# TC1014.net
KiCad netlist of a schematic drawn in EAGLE
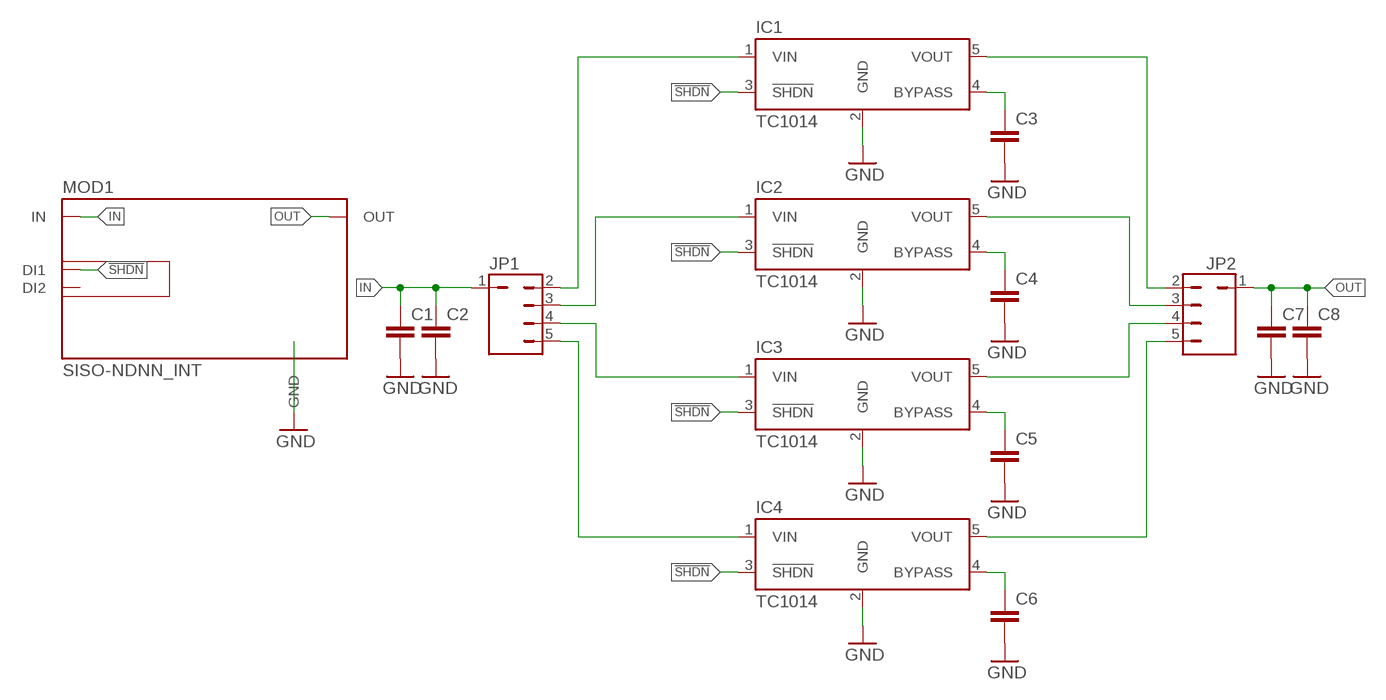
[diagram p0: schematic, sheet 1]

(export (version "E")
  (design (tool "Eeschema 10.0.6"))
  (components
    (comp (ref "C1")
      (value "C-EUC0805")
      (footprint "eagle-import:C0805")
      (libsource (lib "eagle-import") (part "C-EUC0805"))
    )
    (comp (ref "C2")
      (value "C-EUC0805")
      (footprint "eagle-import:C0805")
      (libsource (lib "eagle-import") (part "C-EUC0805"))
    )
    (comp (ref "C3")
      (value "C-EUC0805")
      (footprint "eagle-import:C0805")
      (libsource (lib "eagle-import") (part "C-EUC0805"))
    )
    (comp (ref "C4")
      (value "C-EUC0805")
      (footprint "eagle-import:C0805")
      (libsource (lib "eagle-import") (part "C-EUC0805"))
    )
    (comp (ref "C5")
      (value "C-EUC0805")
      (footprint "eagle-import:C0805")
      (libsource (lib "eagle-import") (part "C-EUC0805"))
    )
    (comp (ref "C6")
      (value "C-EUC0805")
      (footprint "eagle-import:C0805")
      (libsource (lib "eagle-import") (part "C-EUC0805"))
    )
    (comp (ref "C7")
      (value "C-EUC0805")
      (footprint "eagle-import:C0805")
      (libsource (lib "eagle-import") (part "C-EUC0805"))
    )
    (comp (ref "C8")
      (value "C-EUC0805")
      (footprint "eagle-import:C0805")
      (libsource (lib "eagle-import") (part "C-EUC0805"))
    )
    (comp (ref "IC1")
      (value "TC1014")
      (footprint "eagle-import:SOT23-5")
      (libsource (lib "eagle-import") (part "TC1014"))
    )
    (comp (ref "IC2")
      (value "TC1014")
      (footprint "eagle-import:SOT23-5")
      (libsource (lib "eagle-import") (part "TC1014"))
    )
    (comp (ref "IC3")
      (value "TC1014")
      (footprint "eagle-import:SOT23-5")
      (libsource (lib "eagle-import") (part "TC1014"))
    )
    (comp (ref "IC4")
      (value "TC1014")
      (footprint "eagle-import:SOT23-5")
      (libsource (lib "eagle-import") (part "TC1014"))
    )
    (comp (ref "JP1")
      (value "JP4Q")
      (footprint "eagle-import:JP1-4")
      (libsource (lib "eagle-import") (part "JP4Q"))
    )
    (comp (ref "JP2")
      (value "JP4Q")
      (footprint "eagle-import:JP1-4")
      (libsource (lib "eagle-import") (part "JP4Q"))
    )
    (comp (ref "MOD1")
      (value "SISO-NDNN_INT")
      (footprint "eagle-import:SISO-NDNN")
      (libsource (lib "eagle-import") (part "SISO-NDNN_INT"))
    )
  )
  (nets
    (net (code "1") (name "/~{SHDN}") (class "Default")
      (node (ref "IC1") (pin "3") (pinfunction "~{SHDN}_3") (pintype "input"))
      (node (ref "IC2") (pin "3") (pinfunction "~{SHDN}_3") (pintype "input"))
      (node (ref "IC3") (pin "3") (pinfunction "~{SHDN}_3") (pintype "input"))
      (node (ref "IC4") (pin "3") (pinfunction "~{SHDN}_3") (pintype "input"))
      (node (ref "MOD1") (pin "DI1") (pinfunction "DI1_DI1") (pintype "output"))
    )
    (net (code "2") (name "GND") (class "Default")
      (node (ref "C1") (pin "2") (pinfunction "2_2") (pintype "passive"))
      (node (ref "C2") (pin "2") (pinfunction "2_2") (pintype "passive"))
      (node (ref "C3") (pin "2") (pinfunction "2_2") (pintype "passive"))
      (node (ref "C4") (pin "2") (pinfunction "2_2") (pintype "passive"))
      (node (ref "C5") (pin "2") (pinfunction "2_2") (pintype "passive"))
      (node (ref "C6") (pin "2") (pinfunction "2_2") (pintype "passive"))
      (node (ref "C7") (pin "2") (pinfunction "2_2") (pintype "passive"))
      (node (ref "C8") (pin "2") (pinfunction "2_2") (pintype "passive"))
      (node (ref "IC1") (pin "2") (pinfunction "GND_2") (pintype "power_in"))
      (node (ref "IC2") (pin "2") (pinfunction "GND_2") (pintype "power_in"))
      (node (ref "IC3") (pin "2") (pinfunction "GND_2") (pintype "power_in"))
      (node (ref "IC4") (pin "2") (pinfunction "GND_2") (pintype "power_in"))
      (node (ref "MOD1") (pin "GND1") (pinfunction "GND_GND1") (pintype "power_in"))
      (node (ref "MOD1") (pin "GND2") (pinfunction "GND_GND2") (pintype "power_in"))
      (node (ref "MOD1") (pin "GND3") (pinfunction "GND_GND3") (pintype "power_in"))
      (node (ref "MOD1") (pin "GND4") (pinfunction "GND_GND4") (pintype "power_in"))
    )
    (net (code "3") (name "IN") (class "Default")
      (node (ref "C1") (pin "1") (pinfunction "1_1") (pintype "passive"))
      (node (ref "C2") (pin "1") (pinfunction "1_1") (pintype "passive"))
      (node (ref "JP1") (pin "1") (pinfunction "1_1") (pintype "passive"))
      (node (ref "MOD1") (pin "IN1") (pinfunction "IN_IN1") (pintype "output"))
      (node (ref "MOD1") (pin "IN2") (pinfunction "IN_IN2") (pintype "output"))
      (node (ref "MOD1") (pin "IN3") (pinfunction "IN_IN3") (pintype "output"))
      (node (ref "MOD1") (pin "IN4") (pinfunction "IN_IN4") (pintype "output"))
    )
    (net (code "4") (name "Net-(IC1-BYPASS)") (class "Default")
      (node (ref "C3") (pin "1") (pinfunction "1_1") (pintype "passive"))
      (node (ref "IC1") (pin "4") (pinfunction "BYPASS_4") (pintype "bidirectional"))
    )
    (net (code "5") (name "Net-(IC1-VIN)") (class "Default")
      (node (ref "IC1") (pin "1") (pinfunction "VIN_1") (pintype "power_in"))
      (node (ref "JP1") (pin "2") (pinfunction "2_2") (pintype "passive"))
    )
    (net (code "6") (name "Net-(IC1-VOUT)") (class "Default")
      (node (ref "IC1") (pin "5") (pinfunction "VOUT_5") (pintype "power_in"))
      (node (ref "JP2") (pin "2") (pinfunction "2_2") (pintype "passive"))
    )
    (net (code "7") (name "Net-(IC2-BYPASS)") (class "Default")
      (node (ref "C4") (pin "1") (pinfunction "1_1") (pintype "passive"))
      (node (ref "IC2") (pin "4") (pinfunction "BYPASS_4") (pintype "bidirectional"))
    )
    (net (code "8") (name "Net-(IC2-VIN)") (class "Default")
      (node (ref "IC2") (pin "1") (pinfunction "VIN_1") (pintype "power_in"))
      (node (ref "JP1") (pin "3") (pinfunction "3_3") (pintype "passive"))
    )
    (net (code "9") (name "Net-(IC2-VOUT)") (class "Default")
      (node (ref "IC2") (pin "5") (pinfunction "VOUT_5") (pintype "power_in"))
      (node (ref "JP2") (pin "3") (pinfunction "3_3") (pintype "passive"))
    )
    (net (code "10") (name "Net-(IC3-BYPASS)") (class "Default")
      (node (ref "C5") (pin "1") (pinfunction "1_1") (pintype "passive"))
      (node (ref "IC3") (pin "4") (pinfunction "BYPASS_4") (pintype "bidirectional"))
    )
    (net (code "11") (name "Net-(IC3-VIN)") (class "Default")
      (node (ref "IC3") (pin "1") (pinfunction "VIN_1") (pintype "power_in"))
      (node (ref "JP1") (pin "4") (pinfunction "4_4") (pintype "passive"))
    )
    (net (code "12") (name "Net-(IC3-VOUT)") (class "Default")
      (node (ref "IC3") (pin "5") (pinfunction "VOUT_5") (pintype "power_in"))
      (node (ref "JP2") (pin "4") (pinfunction "4_4") (pintype "passive"))
    )
    (net (code "13") (name "Net-(IC4-BYPASS)") (class "Default")
      (node (ref "C6") (pin "1") (pinfunction "1_1") (pintype "passive"))
      (node (ref "IC4") (pin "4") (pinfunction "BYPASS_4") (pintype "bidirectional"))
    )
    (net (code "14") (name "Net-(IC4-VIN)") (class "Default")
      (node (ref "IC4") (pin "1") (pinfunction "VIN_1") (pintype "power_in"))
      (node (ref "JP1") (pin "5") (pinfunction "5_5") (pintype "passive"))
    )
    (net (code "15") (name "Net-(IC4-VOUT)") (class "Default")
      (node (ref "IC4") (pin "5") (pinfunction "VOUT_5") (pintype "power_in"))
      (node (ref "JP2") (pin "5") (pinfunction "5_5") (pintype "passive"))
    )
    (net (code "16") (name "OUT") (class "Default")
      (node (ref "C7") (pin "1") (pinfunction "1_1") (pintype "passive"))
      (node (ref "C8") (pin "1") (pinfunction "1_1") (pintype "passive"))
      (node (ref "JP2") (pin "1") (pinfunction "1_1") (pintype "passive"))
      (node (ref "MOD1") (pin "OUT1") (pinfunction "OUT_OUT1") (pintype "input"))
      (node (ref "MOD1") (pin "OUT2") (pinfunction "OUT_OUT2") (pintype "input"))
      (node (ref "MOD1") (pin "OUT3") (pinfunction "OUT_OUT3") (pintype "input"))
      (node (ref "MOD1") (pin "OUT4") (pinfunction "OUT_OUT4") (pintype "input"))
    )
    (net (code "17") (name "unconnected-(MOD1-PadDI2)") (class "Default")
      (node (ref "MOD1") (pin "DI2") (pinfunction "DI2_DI2") (pintype "output"))
    )
  )
)
